# Controller_Sheet.net
KiCad netlist of a schematic drawn in Altium Designer
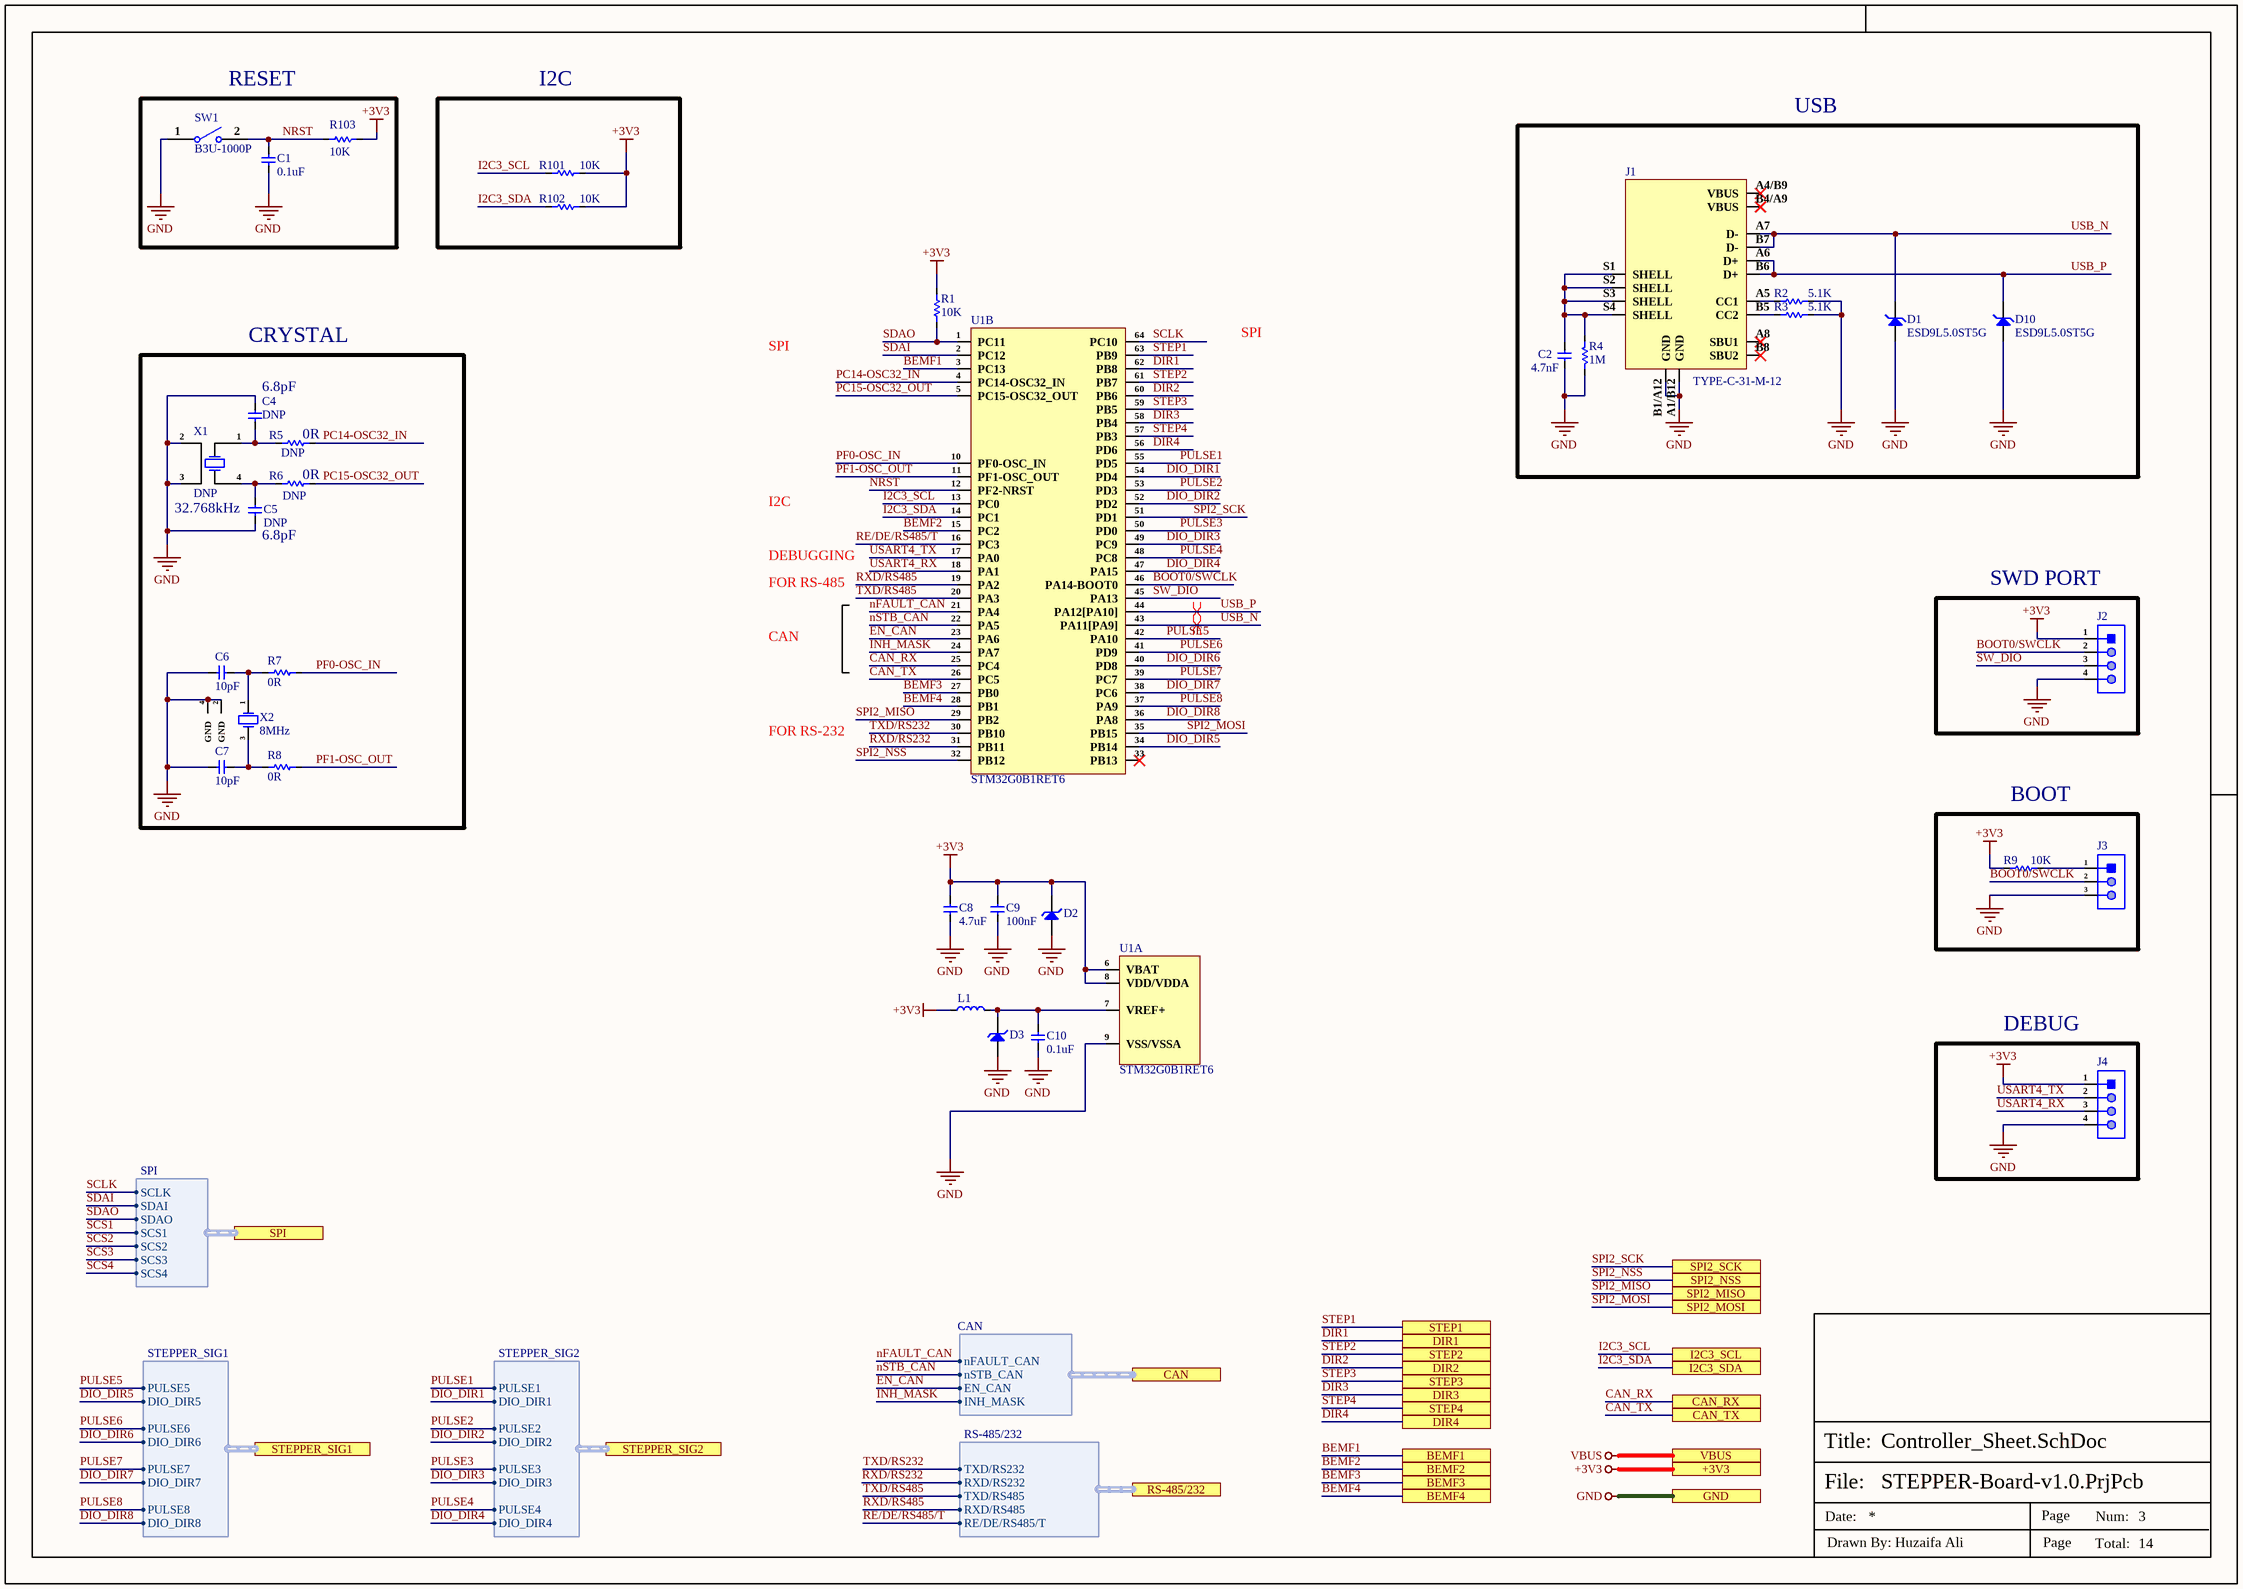
[diagram p0: Controller_Sheet.SchDoc]

(export (version "E")
  (design (tool "Eeschema 10.0.6"))
  (components
    (comp (ref "C1")
      (value "0.1uF")
      (footprint "Cap-0402")
      (description "CAP CER 0.1UF 16V X7R 0402")
      (fields
        (field (name "MANUFACTURER") "Yageo")
        (field (name "MANUFACTURER PART NUMBER") "CC0402JRX7R7BB104")
      )
      (libsource (lib "eSpark Libraries") (part "CC0402JRX7R7BB104"))
    )
    (comp (ref "C2")
      (value "4.7nF")
      (footprint "Cap-0603")
      (description "CAP CER 4700PF 50V C0G/NPO 0603")
      (fields
        (field (name "MANUFACTURER") "Yageo")
        (field (name "MANUFACTURER PART NUMBER") "CC0603JRNPO9BN472")
      )
      (libsource (lib "eSpark_centralized_Library(2022)") (part "CC0603JRNPO9BN472"))
    )
    (comp (ref "C4")
      (value "DNP")
      (footprint "Cap-0402")
      (description "CAP CER 6.8PF 50V C0G/NPO 0402")
      (fields
        (field (name "MANUFACTURER") "Yageo")
        (field (name "MANUFACTURER PART NUMBER") "CC0402CRNPO9BN6R8")
      )
      (libsource (lib "eSpark Libraries") (part "CC0402CRNPO9BN6R8"))
    )
    (comp (ref "C5")
      (value "DNP")
      (footprint "Cap-0402")
      (description "CAP CER 6.8PF 50V C0G/NPO 0402")
      (fields
        (field (name "MANUFACTURER") "Yageo")
        (field (name "MANUFACTURER PART NUMBER") "CC0402CRNPO9BN6R8")
      )
      (libsource (lib "eSpark Libraries") (part "CC0402CRNPO9BN6R8"))
    )
    (comp (ref "C6")
      (value "10pF")
      (footprint "Cap-0402")
      (description "CAP CER 10PF 50V C0G/NP0 0402")
      (fields
        (field (name "MANUFACTURER") "Murata")
        (field (name "MANUFACTURER PART NUMBER") "GRM1555C1H100JA01D")
      )
      (libsource (lib "eSpark Libraries") (part "GRM1555C1H100JA01D"))
    )
    (comp (ref "C7")
      (value "10pF")
      (footprint "Cap-0402")
      (description "CAP CER 10PF 50V C0G/NP0 0402")
      (fields
        (field (name "MANUFACTURER") "Murata")
        (field (name "MANUFACTURER PART NUMBER") "GRM1555C1H100JA01D")
      )
      (libsource (lib "eSpark Libraries") (part "GRM1555C1H100JA01D"))
    )
    (comp (ref "C8")
      (value "4.7uF")
      (footprint "Cap-0402")
      (description "CAP CER 4.7UF 10V X5R 0402")
      (fields
        (field (name "MANUFACTURER") "Yageo")
        (field (name "MANUFACTURER PART NUMBER") "CC0402KRX5R6BB475")
      )
      (libsource (lib "eSpark Libraries") (part "CC0402KRX5R6BB475"))
    )
    (comp (ref "C9")
      (value "100nF")
      (footprint "cap-0402")
      (description "CAP CER 0.1UF 50V X7R 0402")
      (fields
        (field (name "MANUFACTURER") "TDK")
        (field (name "MANUFACTURER PART NUMBER") "C1005X7R1H104KT000F")
      )
      (libsource (lib "eSpark Libraries") (part "C1005X7R1H104KT000F"))
    )
    (comp (ref "C10")
      (value "0.1uF")
      (footprint "Cap-0402")
      (description "CAP CER 0.1UF 16V X7R 0402")
      (fields
        (field (name "MANUFACTURER") "Yageo")
        (field (name "MANUFACTURER PART NUMBER") "CC0402JRX7R7BB104")
      )
      (libsource (lib "eSpark Libraries") (part "CC0402JRX7R7BB104"))
    )
    (comp (ref "D1")
      (value "ESD9L5.0ST5G")
      (footprint "SOD-923.")
      (description "TVS DIODE 5V 9.8V SOD923")
      (fields (field (name "MANUFACTURER") "ON Semiconductor") (field (name "LCSC PART NUMBER") "C82326"))
      (libsource (lib "eSpark Libraries") (part "ESD9L5.0ST5G"))
    )
    (comp (ref "D2")
      (value "AZ3003-01G")
      (footprint "SOD-123")
      (description "TVS SURGE PROTECTOR 1-CH 3.3V")
      (fields (field (name "MANUFACTURER") "Amazing"))
      (libsource (lib "eSpark Libraries") (part "AZ3003-01G"))
    )
    (comp (ref "D3")
      (value "AZ3003-01G")
      (footprint "SOD-123")
      (description "TVS SURGE PROTECTOR 1-CH 3.3V")
      (fields (field (name "MANUFACTURER") "Amazing"))
      (libsource (lib "eSpark Libraries") (part "AZ3003-01G"))
    )
    (comp (ref "D10")
      (value "ESD9L5.0ST5G")
      (footprint "SOD-923.")
      (description "TVS DIODE 5V 9.8V SOD923")
      (fields (field (name "MANUFACTURER") "ON Semiconductor") (field (name "LCSC PART NUMBER") "C82326"))
      (libsource (lib "eSpark Libraries") (part "ESD9L5.0ST5G"))
    )
    (comp (ref "J1")
      (value "TYPE-C-31-M-12")
      (footprint "TYPE-C-31-M-12_")
      (description "5A 1 16P Female Type-C SMD USB Connectors ROHS")
      (fields
        (field (name "MANUFACTURER") "Korean Hroparts Elec")
        (field (name "LCSC PART NUMBER") "C165948")
      )
      (libsource (lib "eSpark Libraries") (part "TYPE-C-31-M-12"))
    )
    (comp (ref "J2")
      (value "X6511WV-04H-C60D30")
      (footprint "HDR1X4_")
      (fields (field (name "MANUFACTURER") "XKB") (field (name "LCSC PART NUMBER") "C706876"))
      (libsource (lib "eSpark Libraries") (part "X6511WV-04H-C60D30"))
    )
    (comp (ref "J3")
      (value "68000-103HLF")
      (footprint "HDR1X3_")
      (description "CONN HEADER VERT 3POS 2.54MM")
      (fields (field (name "LCSC PART NUMBER") "C168677"))
      (libsource (lib "eSpark Libraries") (part "68000-103HLF"))
    )
    (comp (ref "J4")
      (value "X6511WV-04H-C60D30")
      (footprint "HDR1X4_")
      (fields (field (name "MANUFACTURER") "XKB") (field (name "LCSC PART NUMBER") "C706876"))
      (libsource (lib "eSpark Libraries") (part "X6511WV-04H-C60D30"))
    )
    (comp (ref "L1")
      (value "BLM15AG601SN1D")
      (footprint "IND-0402")
      (description "FERRITE BEAD 600 OHM 0402 1LN")
      (fields (field (name "MANUFACTURER") "Murata") (field (name "TOLERANCE") "25%"))
      (libsource (lib "eSpark Libraries") (part "BLM15AG601SN1D"))
    )
    (comp (ref "R1")
      (value "10K")
      (footprint "Res-0402")
      (description "RES 10K OHM 1% 1/16W 0402")
      (fields
        (field (name "MANUFACTURER") "Yageo")
        (field (name "MANUFACTURER PART NUMBER") "RC0402FR-0710KL")
      )
      (libsource (lib "eSpark Libraries") (part "RC0402FR-0710KL"))
    )
    (comp (ref "R2")
      (value "5.1K")
      (footprint "Res-0402")
      (description "RES 5.1K OHM 1% 1/16W 0402")
      (fields
        (field (name "MANUFACTURER") "Yageo")
        (field (name "MANUFACTURER PART NUMBER") "RC0402FR-075K1L")
      )
      (libsource (lib "eSpark Libraries") (part "RC0402FR-075K1L"))
    )
    (comp (ref "R3")
      (value "5.1K")
      (footprint "Res-0402")
      (description "RES 5.1K OHM 1% 1/16W 0402")
      (fields
        (field (name "MANUFACTURER") "Yageo")
        (field (name "MANUFACTURER PART NUMBER") "RC0402FR-075K1L")
      )
      (libsource (lib "eSpark Libraries") (part "RC0402FR-075K1L"))
    )
    (comp (ref "R4")
      (value "1M")
      (footprint "Res-0402")
      (description "RES SMD 1M OHM 5% 1/16W 0402")
      (fields
        (field (name "MANUFACTURER") "Yageo")
        (field (name "MANUFACTURER PART NUMBER") "AF0402JR-071ML")
      )
      (libsource (lib "eSpark_centralized_Library(2022)") (part "AF0402JR-071ML"))
    )
    (comp (ref "R5")
      (value "DNP")
      (footprint "Res-0603")
      (description "RES 0 OHM JUMPER 1/10W 0603")
      (fields
        (field (name "MANUFACTURER") "Yageo")
        (field (name "MANUFACTURER PART NUMBER") "RC0603JR-070RL")
      )
      (libsource (lib "eSpark Libraries") (part "RC0603JR-070RL"))
    )
    (comp (ref "R6")
      (value "DNP")
      (footprint "Res-0603")
      (description "RES 0 OHM JUMPER 1/10W 0603")
      (fields
        (field (name "MANUFACTURER") "Yageo")
        (field (name "MANUFACTURER PART NUMBER") "RC0603JR-070RL")
      )
      (libsource (lib "eSpark Libraries") (part "RC0603JR-070RL"))
    )
    (comp (ref "R7")
      (value "0R")
      (footprint "Res-0603")
      (description "RES 0 OHM JUMPER 1/10W 0603")
      (fields
        (field (name "MANUFACTURER") "Yageo")
        (field (name "MANUFACTURER PART NUMBER") "RC0603JR-070RL")
      )
      (libsource (lib "eSpark Libraries") (part "RC0603JR-070RL"))
    )
    (comp (ref "R8")
      (value "0R")
      (footprint "Res-0603")
      (description "RES 0 OHM JUMPER 1/10W 0603")
      (fields
        (field (name "MANUFACTURER") "Yageo")
        (field (name "MANUFACTURER PART NUMBER") "RC0603JR-070RL")
      )
      (libsource (lib "eSpark Libraries") (part "RC0603JR-070RL"))
    )
    (comp (ref "R9")
      (value "10K")
      (footprint "Res-0402")
      (description "RES 10K OHM 1% 1/16W 0402")
      (fields
        (field (name "MANUFACTURER") "Yageo")
        (field (name "MANUFACTURER PART NUMBER") "RC0402FR-0710KL")
      )
      (libsource (lib "eSpark Libraries") (part "RC0402FR-0710KL"))
    )
    (comp (ref "R101")
      (value "10K")
      (footprint "Res-0402")
      (description "RES 10K OHM 1% 1/16W 0402")
      (fields
        (field (name "MANUFACTURER") "Yageo")
        (field (name "MANUFACTURER PART NUMBER") "RC0402FR-0710KL")
      )
      (libsource (lib "eSpark Libraries") (part "RC0402FR-0710KL"))
    )
    (comp (ref "R102")
      (value "10K")
      (footprint "Res-0402")
      (description "RES 10K OHM 1% 1/16W 0402")
      (fields
        (field (name "MANUFACTURER") "Yageo")
        (field (name "MANUFACTURER PART NUMBER") "RC0402FR-0710KL")
      )
      (libsource (lib "eSpark Libraries") (part "RC0402FR-0710KL"))
    )
    (comp (ref "R103")
      (value "10K")
      (footprint "Res-0402")
      (description "RES 10K OHM 1% 1/16W 0402")
      (fields
        (field (name "MANUFACTURER") "Yageo")
        (field (name "MANUFACTURER PART NUMBER") "RC0402FR-0710KL")
      )
      (libsource (lib "eSpark Libraries") (part "RC0402FR-0710KL"))
    )
    (comp (ref "SW1")
      (value "B3U-1000P")
      (footprint "B3U-1000P")
      (description "SWITCH TACTILE SPST-NO 0.05A 12V")
      (fields (field (name "MANUFACTURER") "Omron") (field (name "LCSC PART NUMBER") "C231329"))
      (libsource (lib "eSpark Libraries") (part "B3U-1000P"))
    )
    (comp (ref "U1")
      (value "STM32G0B1RET6")
      (footprint "LQFP-64(10x10)")
      (description "IC MCU 32BIT 512KB FLASH 64LQFP")
      (fields (field (name "MANUFACTURER") "STMicroelectronics") (field (name "LCSC PART NUMBER") "C2829307"))
      (libsource (lib "eSpark Libraries") (part "STM32G0B1RET6"))
    )
    (comp (ref "X1")
      (value "DNP")
      (footprint "MC-306")
      (description "32.768kHz 12.5pF ±20ppm MC-306 Crystals ROHS")
      (fields
        (field (name "MANUFACTURER") "Seiko Epson")
        (field (name "MANUFACTURER PART NUMBER") "MC-306 32.7680K-A0:ROHS")
      )
      (libsource (lib "eSpark Libraries") (part "MC-306 32.7680K-A0{colon}ROHS"))
    )
    (comp (ref "X2")
      (value "8MHz")
      (footprint "5TJ480000XYLBC_")
      (description "8MHz 18pF ±10ppm SMD5032-4P Crystals ROHS")
      (fields (field (name "MANUFACTURER") "JYJE") (field (name "MANUFACTURER PART NUMBER") "5TJ480000XYLBC"))
      (libsource (lib "eSpark Libraries") (part "5TJ480000XYLBC"))
    )
  )
  (nets
    (net (code "6") (name "+3V3") (class "Default")
      (node (ref "C8") (pin "2") (pinfunction "2_2") (pintype "passive"))
      (node (ref "C9") (pin "2") (pinfunction "2_2") (pintype "passive"))
      (node (ref "D2") (pin "2") (pinfunction "K_2") (pintype "passive"))
      (node (ref "J2") (pin "1") (pinfunction "1_1") (pintype "passive"))
      (node (ref "J4") (pin "1") (pinfunction "1_1") (pintype "passive"))
      (node (ref "L1") (pin "1") (pinfunction "1_1") (pintype "passive"))
      (node (ref "R1") (pin "1") (pinfunction "1_1") (pintype "passive"))
      (node (ref "R101") (pin "1") (pinfunction "1_1") (pintype "passive"))
      (node (ref "R102") (pin "1") (pinfunction "1_1") (pintype "passive"))
      (node (ref "R103") (pin "2") (pinfunction "2_2") (pintype "passive"))
      (node (ref "R9") (pin "2") (pinfunction "2_2") (pintype "passive"))
      (node (ref "U1") (pin "6") (pinfunction "VBAT_6") (pintype "passive"))
      (node (ref "U1") (pin "8") (pinfunction "VDD/VDDA_8") (pintype "passive"))
    )
    (net (code "7") (name "/BEMF1") (class "Default")
      (node (ref "U1") (pin "3") (pinfunction "PC13_3") (pintype "passive"))
    )
    (net (code "8") (name "/BEMF2") (class "Default")
      (node (ref "U1") (pin "15") (pinfunction "PC2_15") (pintype "passive"))
    )
    (net (code "9") (name "/BEMF3") (class "Default")
      (node (ref "U1") (pin "27") (pinfunction "PB0_27") (pintype "passive"))
    )
    (net (code "10") (name "/BEMF4") (class "Default")
      (node (ref "U1") (pin "28") (pinfunction "PB1_28") (pintype "passive"))
    )
    (net (code "11") (name "/BOOT0{slash}SWCLK") (class "Default")
      (node (ref "J2") (pin "2") (pinfunction "2_2") (pintype "passive"))
      (node (ref "J3") (pin "2") (pinfunction "2_2") (pintype "passive"))
      (node (ref "U1") (pin "46") (pinfunction "PA14-BOOT0_46") (pintype "passive"))
    )
    (net (code "12") (name "/CAN_RX") (class "Default")
      (node (ref "U1") (pin "25") (pinfunction "PC4_25") (pintype "passive"))
    )
    (net (code "13") (name "/CAN_TX") (class "Default")
      (node (ref "U1") (pin "26") (pinfunction "PC5_26") (pintype "passive"))
    )
    (net (code "14") (name "/DIO_DIR1") (class "Default")
      (node (ref "U1") (pin "54") (pinfunction "PD4_54") (pintype "passive"))
    )
    (net (code "15") (name "/DIO_DIR2") (class "Default")
      (node (ref "U1") (pin "52") (pinfunction "PD2_52") (pintype "passive"))
    )
    (net (code "16") (name "/DIO_DIR3") (class "Default")
      (node (ref "U1") (pin "49") (pinfunction "PC9_49") (pintype "passive"))
    )
    (net (code "17") (name "/DIO_DIR4") (class "Default")
      (node (ref "U1") (pin "47") (pinfunction "PA15_47") (pintype "passive"))
    )
    (net (code "18") (name "/DIO_DIR5") (class "Default")
      (node (ref "U1") (pin "34") (pinfunction "PB14_34") (pintype "passive"))
    )
    (net (code "19") (name "/DIO_DIR6") (class "Default")
      (node (ref "U1") (pin "40") (pinfunction "PD8_40") (pintype "passive"))
    )
    (net (code "20") (name "/DIO_DIR7") (class "Default")
      (node (ref "U1") (pin "38") (pinfunction "PC6_38") (pintype "passive"))
    )
    (net (code "21") (name "/DIO_DIR8") (class "Default")
      (node (ref "U1") (pin "36") (pinfunction "PA8_36") (pintype "passive"))
    )
    (net (code "22") (name "/DIR1") (class "Default")
      (node (ref "U1") (pin "62") (pinfunction "PB8_62") (pintype "passive"))
    )
    (net (code "23") (name "/DIR2") (class "Default")
      (node (ref "U1") (pin "60") (pinfunction "PB6_60") (pintype "passive"))
    )
    (net (code "24") (name "/DIR3") (class "Default")
      (node (ref "U1") (pin "58") (pinfunction "PB4_58") (pintype "passive"))
    )
    (net (code "25") (name "/DIR4") (class "Default")
      (node (ref "U1") (pin "56") (pinfunction "PD6_56") (pintype "passive"))
    )
    (net (code "26") (name "/EN_CAN") (class "Default")
      (node (ref "U1") (pin "23") (pinfunction "PA6_23") (pintype "passive"))
    )
    (net (code "27") (name "/I2C3_SCL") (class "Default")
      (node (ref "R101") (pin "2") (pinfunction "2_2") (pintype "passive"))
      (node (ref "U1") (pin "13") (pinfunction "PC0_13") (pintype "passive"))
    )
    (net (code "28") (name "/I2C3_SDA") (class "Default")
      (node (ref "R102") (pin "2") (pinfunction "2_2") (pintype "passive"))
      (node (ref "U1") (pin "14") (pinfunction "PC1_14") (pintype "passive"))
    )
    (net (code "29") (name "/INH_MASK") (class "Default")
      (node (ref "U1") (pin "24") (pinfunction "PA7_24") (pintype "passive"))
    )
    (net (code "30") (name "/NRST") (class "Default")
      (node (ref "C1") (pin "2") (pinfunction "2_2") (pintype "passive"))
      (node (ref "R103") (pin "1") (pinfunction "1_1") (pintype "passive"))
      (node (ref "SW1") (pin "2") (pinfunction "2_2") (pintype "passive"))
      (node (ref "U1") (pin "12") (pinfunction "PF2-NRST_12") (pintype "passive"))
    )
    (net (code "31") (name "/PC14-OSC32_IN") (class "Default")
      (node (ref "R5") (pin "2") (pinfunction "2_2") (pintype "passive"))
      (node (ref "U1") (pin "4") (pinfunction "PC14-OSC32_IN_4") (pintype "passive"))
    )
    (net (code "32") (name "/PC15-OSC32_OUT") (class "Default")
      (node (ref "R6") (pin "2") (pinfunction "2_2") (pintype "passive"))
      (node (ref "U1") (pin "5") (pinfunction "PC15-OSC32_OUT_5") (pintype "passive"))
    )
    (net (code "33") (name "/PF0-OSC_IN") (class "Default")
      (node (ref "R7") (pin "2") (pinfunction "2_2") (pintype "passive"))
      (node (ref "U1") (pin "10") (pinfunction "PF0-OSC_IN_10") (pintype "passive"))
    )
    (net (code "34") (name "/PF1-OSC_OUT") (class "Default")
      (node (ref "R8") (pin "2") (pinfunction "2_2") (pintype "passive"))
      (node (ref "U1") (pin "11") (pinfunction "PF1-OSC_OUT_11") (pintype "passive"))
    )
    (net (code "35") (name "/PULSE1") (class "Default")
      (node (ref "U1") (pin "55") (pinfunction "PD5_55") (pintype "passive"))
    )
    (net (code "36") (name "/PULSE2") (class "Default")
      (node (ref "U1") (pin "53") (pinfunction "PD3_53") (pintype "passive"))
    )
    (net (code "37") (name "/PULSE3") (class "Default")
      (node (ref "U1") (pin "50") (pinfunction "PD0_50") (pintype "passive"))
    )
    (net (code "38") (name "/PULSE4") (class "Default")
      (node (ref "U1") (pin "48") (pinfunction "PC8_48") (pintype "passive"))
    )
    (net (code "39") (name "/PULSE5") (class "Default")
      (node (ref "U1") (pin "42") (pinfunction "PA10_42") (pintype "passive"))
    )
    (net (code "40") (name "/PULSE6") (class "Default")
      (node (ref "U1") (pin "41") (pinfunction "PD9_41") (pintype "passive"))
    )
    (net (code "41") (name "/PULSE7") (class "Default")
      (node (ref "U1") (pin "39") (pinfunction "PC7_39") (pintype "passive"))
    )
    (net (code "42") (name "/PULSE8") (class "Default")
      (node (ref "U1") (pin "37") (pinfunction "PA9_37") (pintype "passive"))
    )
    (net (code "43") (name "/RE{slash}DE{slash}RS485{slash}T") (class "Default")
      (node (ref "U1") (pin "16") (pinfunction "PC3_16") (pintype "passive"))
    )
    (net (code "44") (name "/RXD{slash}RS232") (class "Default")
      (node (ref "U1") (pin "31") (pinfunction "PB11_31") (pintype "passive"))
    )
    (net (code "45") (name "/RXD{slash}RS485") (class "Default")
      (node (ref "U1") (pin "19") (pinfunction "PA2_19") (pintype "passive"))
    )
    (net (code "46") (name "/SCLK") (class "Default")
      (node (ref "U1") (pin "64") (pinfunction "PC10_64") (pintype "passive"))
    )
    (net (code "51") (name "/SDAI") (class "Default")
      (node (ref "U1") (pin "2") (pinfunction "PC12_2") (pintype "passive"))
    )
    (net (code "52") (name "/SDAO") (class "Default")
      (node (ref "R1") (pin "2") (pinfunction "2_2") (pintype "passive"))
      (node (ref "U1") (pin "1") (pinfunction "PC11_1") (pintype "passive"))
    )
    (net (code "53") (name "/SPI2_MISO") (class "Default")
      (node (ref "U1") (pin "29") (pinfunction "PB2_29") (pintype "passive"))
    )
    (net (code "54") (name "/SPI2_MOSI") (class "Default")
      (node (ref "U1") (pin "35") (pinfunction "PB15_35") (pintype "passive"))
    )
    (net (code "55") (name "/SPI2_NSS") (class "Default")
      (node (ref "U1") (pin "32") (pinfunction "PB12_32") (pintype "passive"))
    )
    (net (code "56") (name "/SPI2_SCK") (class "Default")
      (node (ref "U1") (pin "51") (pinfunction "PD1_51") (pintype "passive"))
    )
    (net (code "57") (name "/STEP1") (class "Default")
      (node (ref "U1") (pin "63") (pinfunction "PB9_63") (pintype "passive"))
    )
    (net (code "58") (name "/STEP2") (class "Default")
      (node (ref "U1") (pin "61") (pinfunction "PB7_61") (pintype "passive"))
    )
    (net (code "59") (name "/STEP3") (class "Default")
      (node (ref "U1") (pin "59") (pinfunction "PB5_59") (pintype "passive"))
    )
    (net (code "60") (name "/STEP4") (class "Default")
      (node (ref "U1") (pin "57") (pinfunction "PB3_57") (pintype "passive"))
    )
    (net (code "61") (name "/SW_DIO") (class "Default")
      (node (ref "J2") (pin "3") (pinfunction "3_3") (pintype "passive"))
      (node (ref "U1") (pin "45") (pinfunction "PA13_45") (pintype "passive"))
    )
    (net (code "62") (name "/TXD{slash}RS232") (class "Default")
      (node (ref "U1") (pin "30") (pinfunction "PB10_30") (pintype "passive"))
    )
    (net (code "63") (name "/TXD{slash}RS485") (class "Default")
      (node (ref "U1") (pin "20") (pinfunction "PA3_20") (pintype "passive"))
    )
    (net (code "64") (name "/USART4_RX") (class "Default")
      (node (ref "J4") (pin "3") (pinfunction "3_3") (pintype "passive"))
      (node (ref "U1") (pin "18") (pinfunction "PA1_18") (pintype "passive"))
    )
    (net (code "65") (name "/USART4_TX") (class "Default")
      (node (ref "J4") (pin "2") (pinfunction "2_2") (pintype "passive"))
      (node (ref "U1") (pin "17") (pinfunction "PA0_17") (pintype "passive"))
    )
    (net (code "66") (name "/USB_N") (class "Default")
      (node (ref "D1") (pin "1") (pinfunction "K_1") (pintype "passive"))
      (node (ref "J1") (pin "A7") (pinfunction "D-_A7") (pintype "passive"))
      (node (ref "J1") (pin "B7") (pinfunction "D-_B7") (pintype "passive"))
      (node (ref "U1") (pin "43") (pinfunction "PA11[PA9]_43") (pintype "passive"))
    )
    (net (code "67") (name "/USB_P") (class "Default")
      (node (ref "D10") (pin "1") (pinfunction "K_1") (pintype "passive"))
      (node (ref "J1") (pin "A6") (pinfunction "D+_A6") (pintype "passive"))
      (node (ref "J1") (pin "B6") (pinfunction "D+_B6") (pintype "passive"))
      (node (ref "U1") (pin "44") (pinfunction "PA12[PA10]_44") (pintype "passive"))
    )
    (net (code "68") (name "/nFAULT_CAN") (class "Default")
      (node (ref "U1") (pin "21") (pinfunction "PA4_21") (pintype "passive"))
    )
    (net (code "69") (name "/nSTB_CAN") (class "Default")
      (node (ref "U1") (pin "22") (pinfunction "PA5_22") (pintype "passive"))
    )
    (net (code "75") (name "GND") (class "Default")
      (node (ref "C1") (pin "1") (pinfunction "1_1") (pintype "passive"))
      (node (ref "C10") (pin "1") (pinfunction "1_1") (pintype "passive"))
      (node (ref "C2") (pin "1") (pinfunction "1_1") (pintype "passive"))
      (node (ref "C4") (pin "1") (pinfunction "1_1") (pintype "passive"))
      (node (ref "C5") (pin "2") (pinfunction "2_2") (pintype "passive"))
      (node (ref "C6") (pin "2") (pinfunction "2_2") (pintype "passive"))
      (node (ref "C7") (pin "2") (pinfunction "2_2") (pintype "passive"))
      (node (ref "C8") (pin "1") (pinfunction "1_1") (pintype "passive"))
      (node (ref "C9") (pin "1") (pinfunction "1_1") (pintype "passive"))
      (node (ref "D1") (pin "2") (pinfunction "A_2") (pintype "passive"))
      (node (ref "D10") (pin "2") (pinfunction "A_2") (pintype "passive"))
      (node (ref "D2") (pin "1") (pinfunction "A_1") (pintype "passive"))
      (node (ref "D3") (pin "1") (pinfunction "A_1") (pintype "passive"))
      (node (ref "J1") (pin "A1/B12") (pinfunction "GND_A1/B12") (pintype "power_in"))
      (node (ref "J1") (pin "B1/A12") (pinfunction "GND_B1/A12") (pintype "power_in"))
      (node (ref "J2") (pin "4") (pinfunction "4_4") (pintype "passive"))
      (node (ref "J3") (pin "3") (pinfunction "3_3") (pintype "passive"))
      (node (ref "J4") (pin "4") (pinfunction "4_4") (pintype "passive"))
      (node (ref "R2") (pin "2") (pinfunction "2_2") (pintype "passive"))
      (node (ref "R3") (pin "2") (pinfunction "2_2") (pintype "passive"))
      (node (ref "R4") (pin "2") (pinfunction "2_2") (pintype "passive"))
      (node (ref "SW1") (pin "1") (pinfunction "1_1") (pintype "passive"))
      (node (ref "U1") (pin "9") (pinfunction "VSS/VSSA_9") (pintype "passive"))
      (node (ref "X1") (pin "2") (pinfunction "2_2") (pintype "passive"))
      (node (ref "X1") (pin "3") (pinfunction "3_3") (pintype "passive"))
      (node (ref "X2") (pin "2") (pinfunction "GND_2") (pintype "passive"))
      (node (ref "X2") (pin "4") (pinfunction "GND_4") (pintype "passive"))
    )
    (net (code "76") (name "Net-(C2-Pad2)") (class "Default")
      (node (ref "C2") (pin "2") (pinfunction "2_2") (pintype "passive"))
      (node (ref "J1") (pin "S1") (pinfunction "SHELL_S1") (pintype "passive"))
      (node (ref "J1") (pin "S2") (pinfunction "SHELL_S2") (pintype "passive"))
      (node (ref "J1") (pin "S3") (pinfunction "SHELL_S3") (pintype "passive"))
      (node (ref "J1") (pin "S4") (pinfunction "SHELL_S4") (pintype "passive"))
      (node (ref "R4") (pin "1") (pinfunction "1_1") (pintype "passive"))
    )
    (net (code "77") (name "Net-(D3-K)") (class "Default")
      (node (ref "C10") (pin "2") (pinfunction "2_2") (pintype "passive"))
      (node (ref "D3") (pin "2") (pinfunction "K_2") (pintype "passive"))
      (node (ref "L1") (pin "2") (pinfunction "2_2") (pintype "passive"))
      (node (ref "U1") (pin "7") (pinfunction "VREF+_7") (pintype "passive"))
    )
    (net (code "78") (name "Net-(J1-CC1)") (class "Default")
      (node (ref "J1") (pin "A5") (pinfunction "CC1_A5") (pintype "passive"))
      (node (ref "R2") (pin "1") (pinfunction "1_1") (pintype "passive"))
    )
    (net (code "79") (name "Net-(J1-CC2)") (class "Default")
      (node (ref "J1") (pin "B5") (pinfunction "CC2_B5") (pintype "passive"))
      (node (ref "R3") (pin "1") (pinfunction "1_1") (pintype "passive"))
    )
    (net (code "80") (name "Net-(J3-Pad1)") (class "Default")
      (node (ref "J3") (pin "1") (pinfunction "1_1") (pintype "passive"))
      (node (ref "R9") (pin "1") (pinfunction "1_1") (pintype "passive"))
    )
    (net (code "81") (name "Net-(X1-OSC1)") (class "Default")
      (node (ref "C4") (pin "2") (pinfunction "2_2") (pintype "passive"))
      (node (ref "R5") (pin "1") (pinfunction "1_1") (pintype "passive"))
      (node (ref "X1") (pin "1") (pinfunction "OSC1_1") (pintype "passive"))
    )
    (net (code "82") (name "Net-(X1-OSC2)") (class "Default")
      (node (ref "C5") (pin "1") (pinfunction "1_1") (pintype "passive"))
      (node (ref "R6") (pin "1") (pinfunction "1_1") (pintype "passive"))
      (node (ref "X1") (pin "4") (pinfunction "OSC2_4") (pintype "passive"))
    )
    (net (code "83") (name "Net-(X2-OSC1)") (class "Default")
      (node (ref "C6") (pin "1") (pinfunction "1_1") (pintype "passive"))
      (node (ref "R7") (pin "1") (pinfunction "1_1") (pintype "passive"))
      (node (ref "X2") (pin "1") (pinfunction "OSC1_1") (pintype "passive"))
    )
    (net (code "84") (name "Net-(X2-OSC2)") (class "Default")
      (node (ref "C7") (pin "1") (pinfunction "1_1") (pintype "passive"))
      (node (ref "R8") (pin "1") (pinfunction "1_1") (pintype "passive"))
      (node (ref "X2") (pin "3") (pinfunction "OSC2_3") (pintype "passive"))
    )
    (net (code "86") (name "unconnected-(J1-SBU1-PadA8)") (class "Default")
      (node (ref "J1") (pin "A8") (pinfunction "SBU1_A8") (pintype "passive+no_connect"))
    )
    (net (code "87") (name "unconnected-(J1-SBU2-PadB8)") (class "Default")
      (node (ref "J1") (pin "B8") (pinfunction "SBU2_B8") (pintype "passive+no_connect"))
    )
    (net (code "88") (name "unconnected-(J1-VBUS-PadA4{slash}B9)") (class "Default")
      (node (ref "J1") (pin "A4/B9") (pinfunction "VBUS_A4/B9") (pintype "power_in+no_connect"))
    )
    (net (code "89") (name "unconnected-(J1-VBUS-PadB4{slash}A9)") (class "Default")
      (node (ref "J1") (pin "B4/A9") (pinfunction "VBUS_B4/A9") (pintype "power_in+no_connect"))
    )
    (net (code "90") (name "unconnected-(U1B-PB13-Pad33)") (class "Default")
      (node (ref "U1") (pin "33") (pinfunction "PB13_33") (pintype "passive+no_connect"))
    )
  )
)
